# Display50_Cape.net
KiCad netlist of a schematic drawn in EAGLE
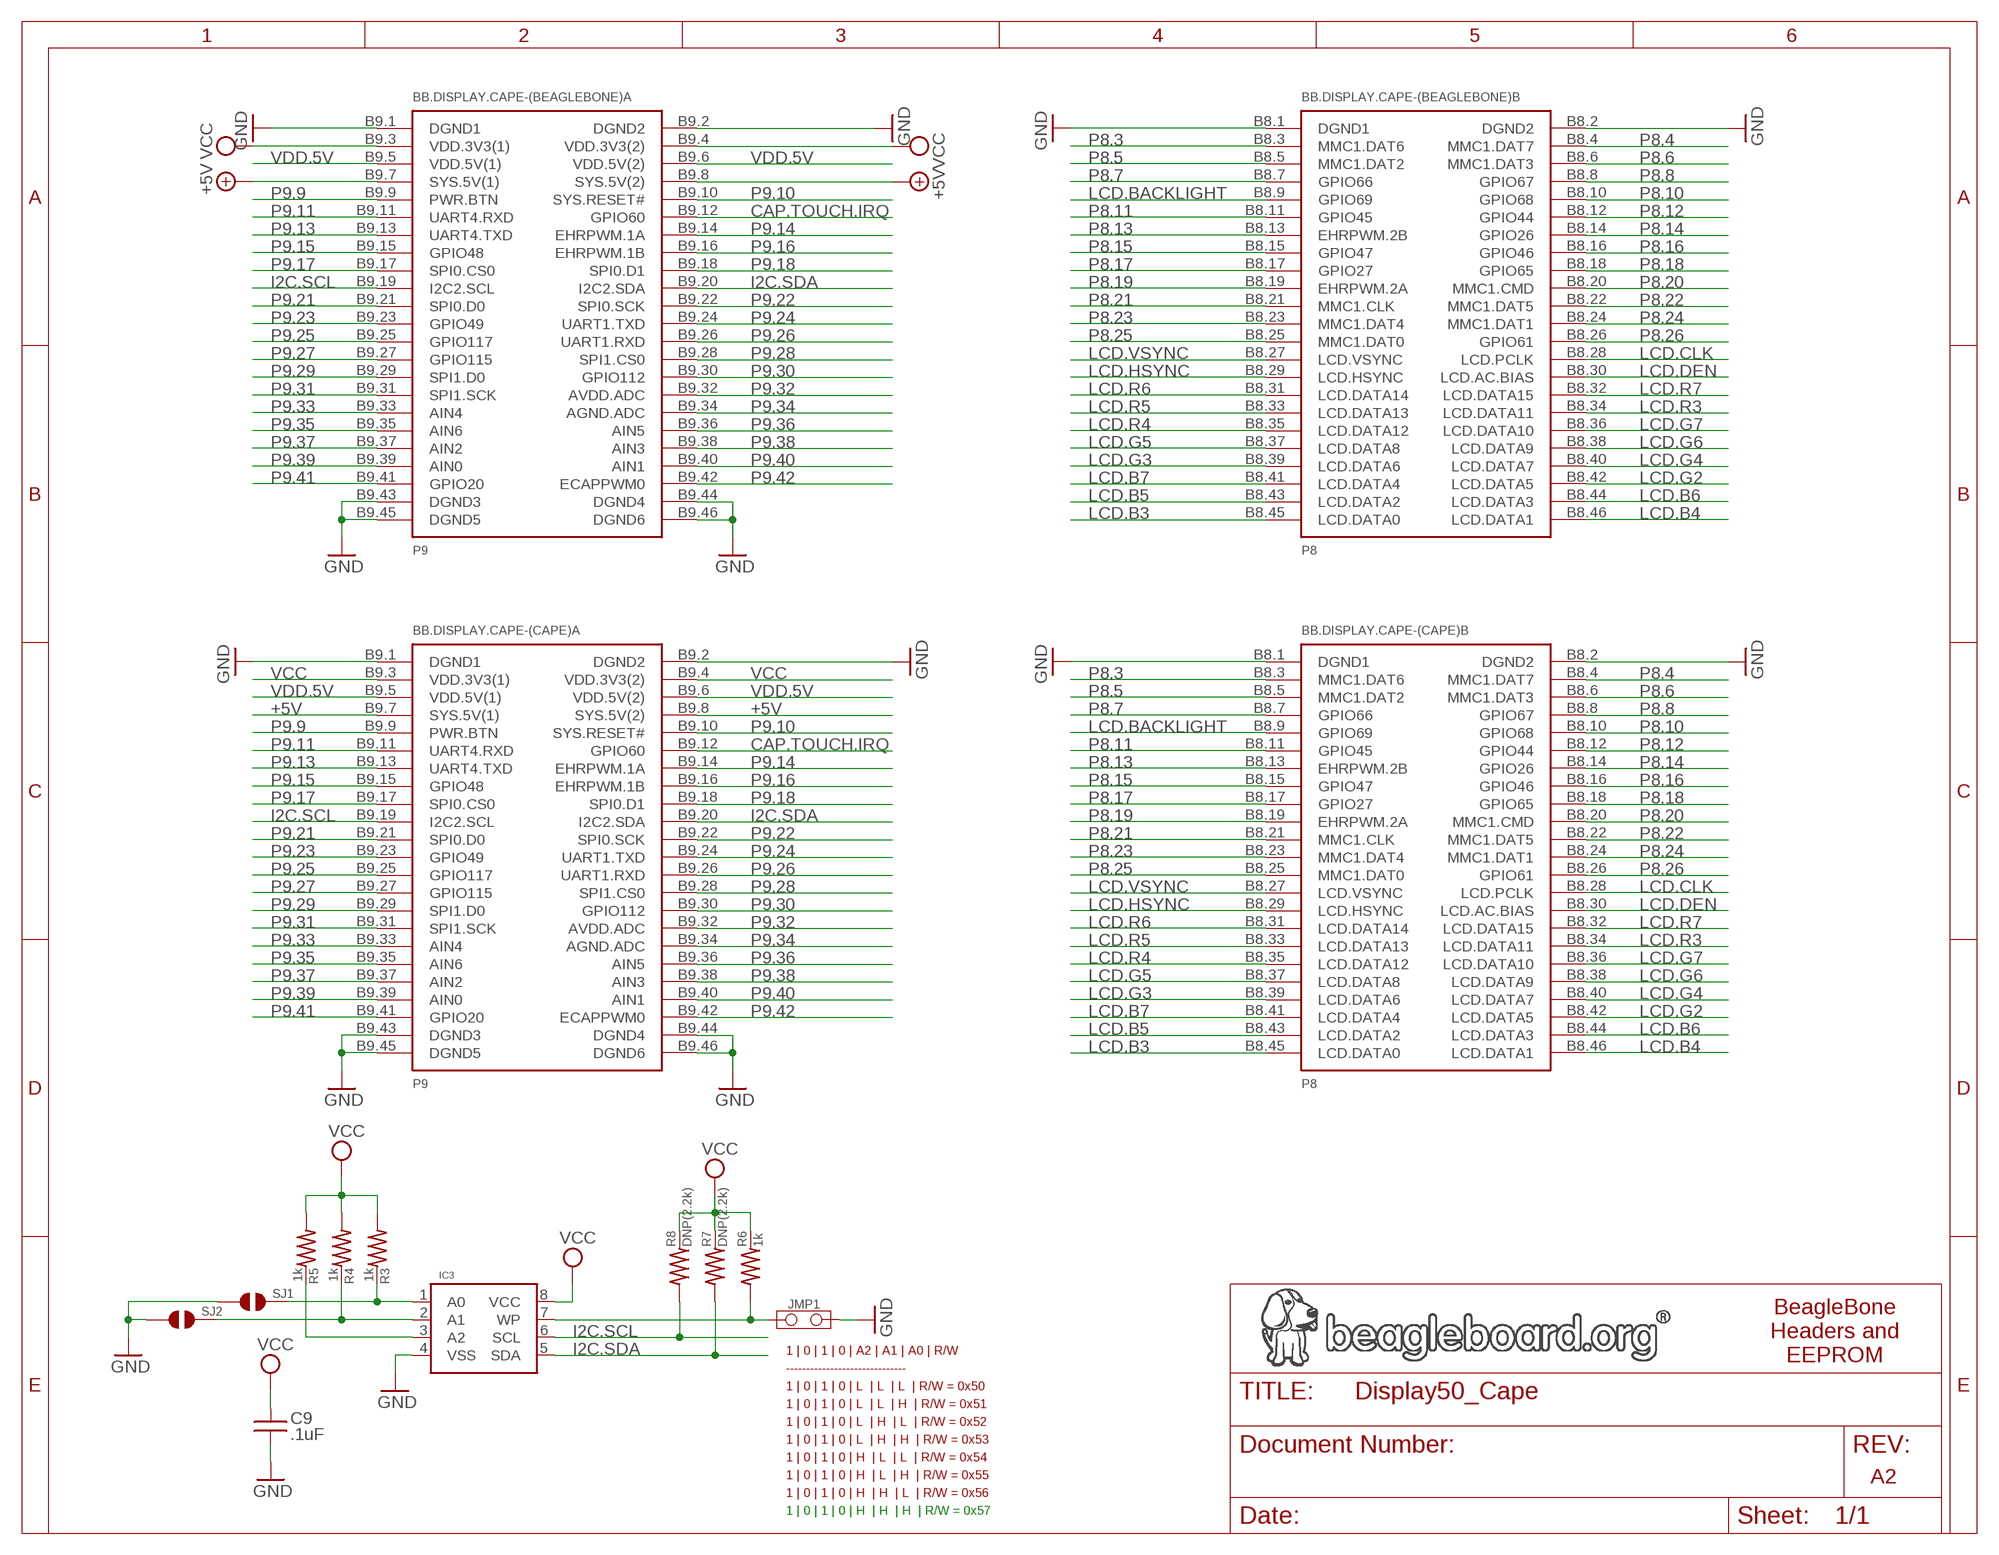
[diagram p0: schematic, sheet 1, part 1 of 2]
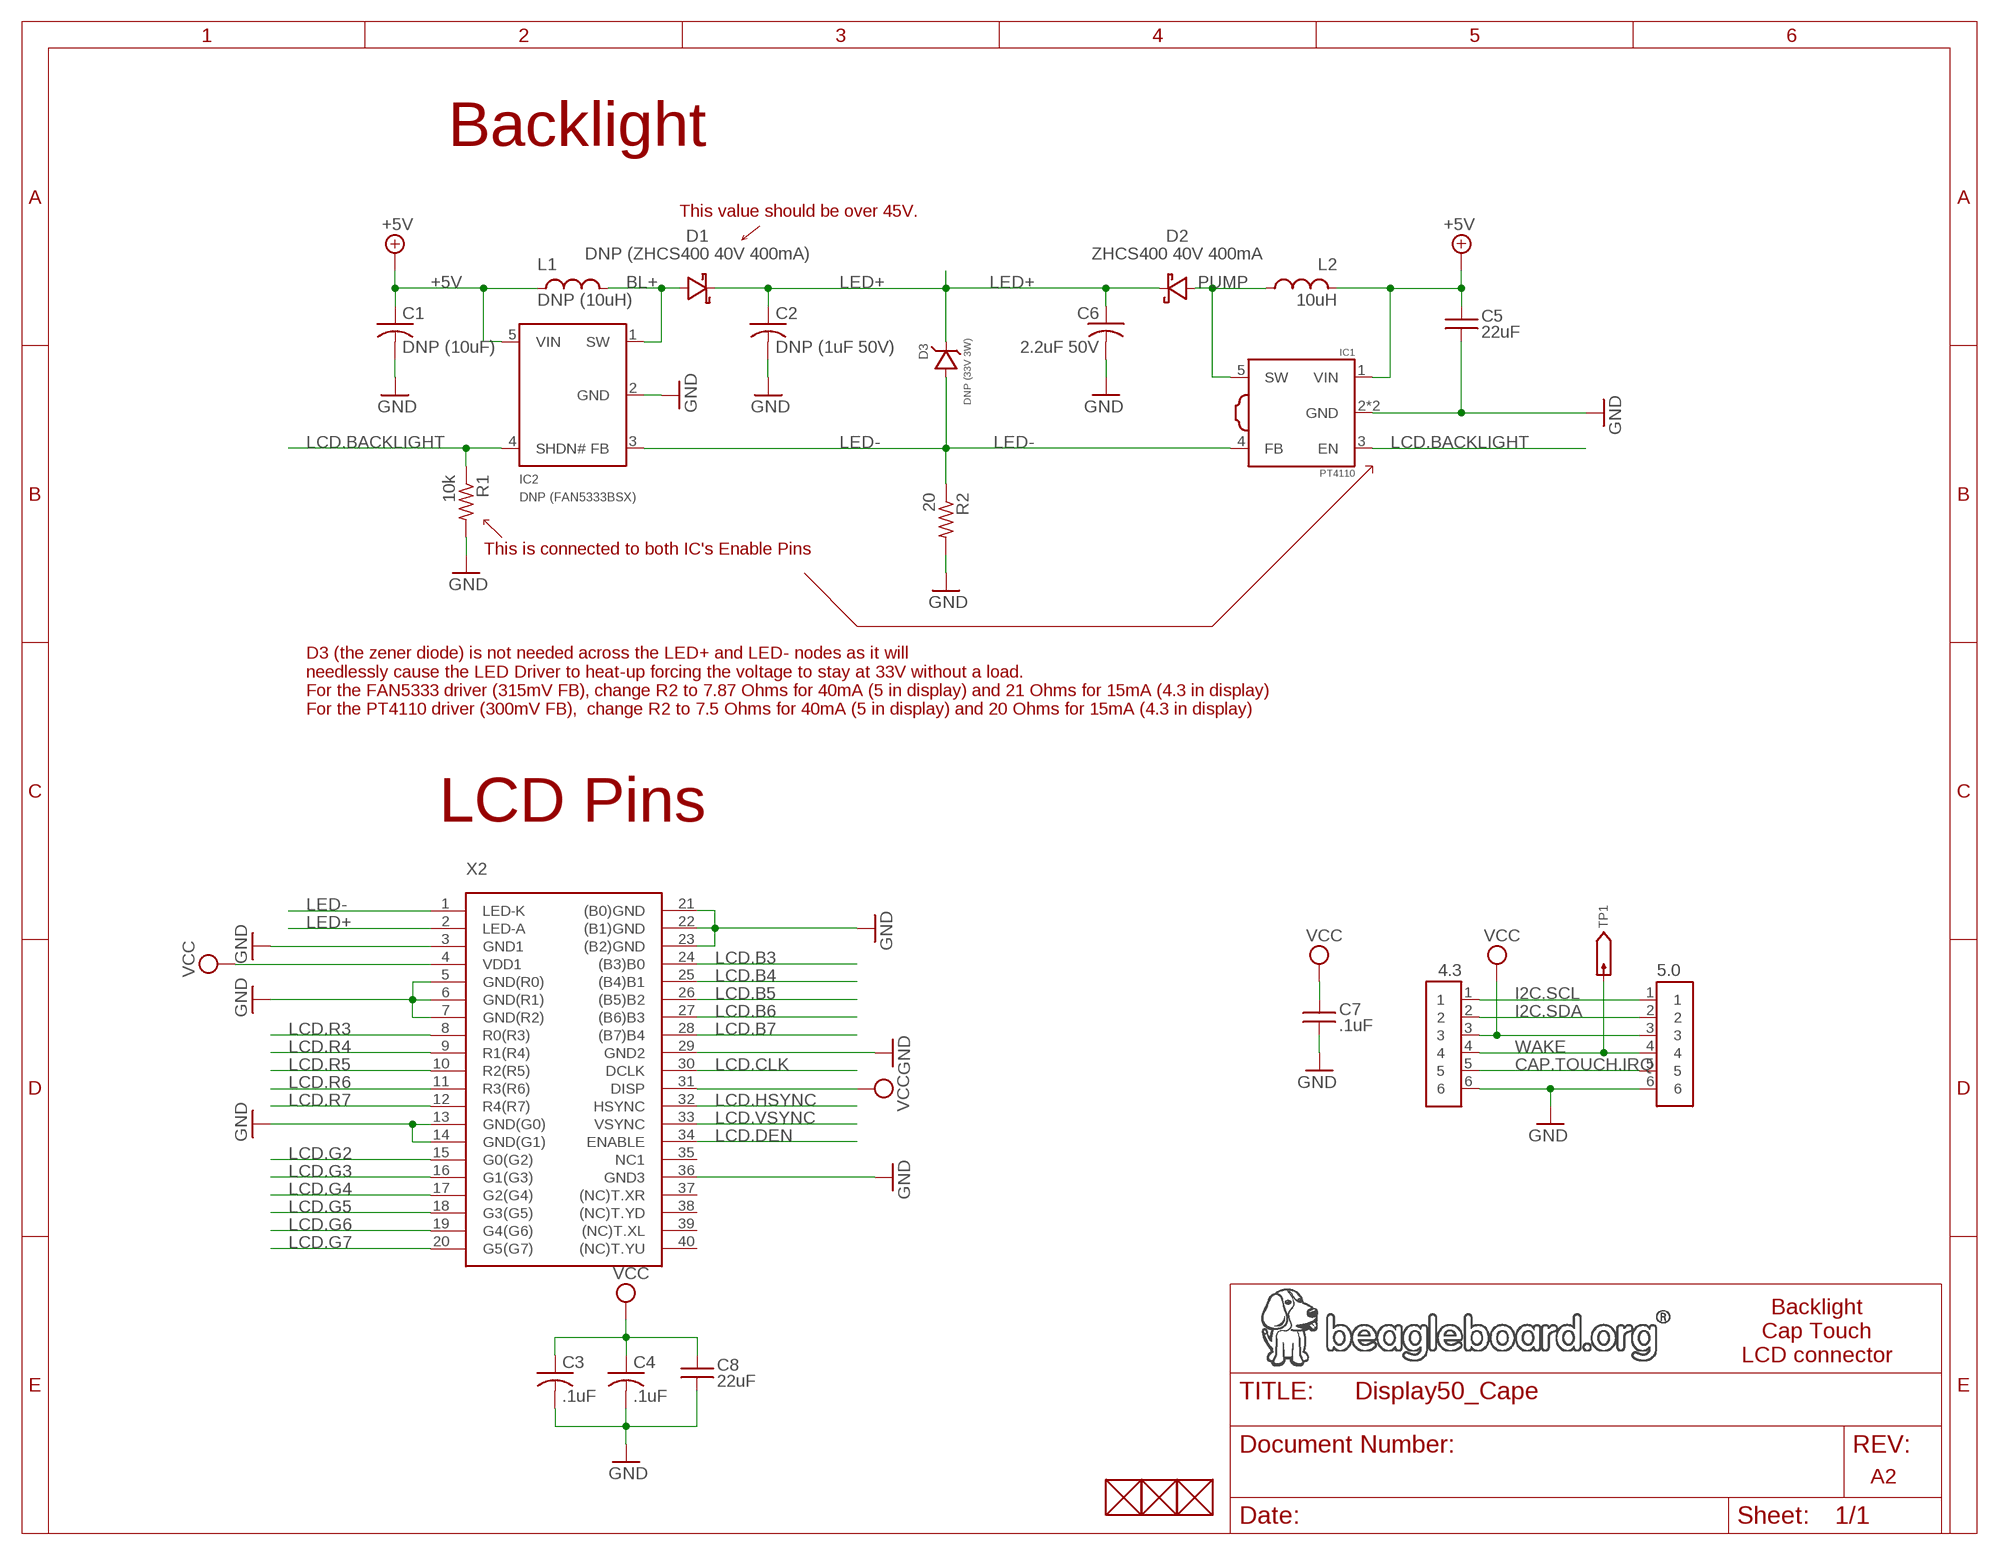
[diagram p1: schematic, sheet 1, part 2 of 2]

(export (version "E")
  (design (tool "Eeschema 10.0.6"))
  (components
    (comp (ref "4.3")
      (value "6-PIN-(0.5MM-PITCH)-FPC-CONNECTOR")
      (footprint "eagle-import:6-PIN-(0.5MM-PITCH)-FPC-CONNECTOR")
      (libsource (lib "eagle-import") (part "6-PIN-(0.5MM-PITCH)-FPC-CONNECTOR"))
    )
    (comp (ref "5.0")
      (value "6-PIN-(0.5MM-PITCH)-FPC-CONNECTOR")
      (footprint "eagle-import:6-PIN-(0.5MM-PITCH)-FPC-CONNECTOR")
      (libsource (lib "eagle-import") (part "6-PIN-(0.5MM-PITCH)-FPC-CONNECTOR"))
    )
    (comp (ref "BB.DISPLAY.CAPE-(BEAGLEBONE)")
      (value "BEAGLEBONE.CAPE.DISPLAY-X.BEAGLEBONE")
      (footprint "eagle-import:BEAGLEBONE.CAPE.DISPLAY-X.BEAGLEBONE")
      (libsource (lib "eagle-import") (part "BEAGLEBONE.CAPE.DISPLAY-X.BEAGLEBONE"))
    )
    (comp (ref "BB.DISPLAY.CAPE-(CAPE)")
      (value "BEAGLEBONE.CAPE.DISPLAY-X.CAPE")
      (footprint "eagle-import:BEAGLEBONE.CAPE.DISPLAY-X.CAPE")
      (libsource (lib "eagle-import") (part "BEAGLEBONE.CAPE.DISPLAY-X.CAPE"))
    )
    (comp (ref "C1")
      (value "DNP (10uF)")
      (footprint "eagle-import:C0603K")
      (libsource (lib "eagle-import") (part "C-USC0603K"))
    )
    (comp (ref "C2")
      (value "DNP (1uF 50V)")
      (footprint "eagle-import:C0805K")
      (libsource (lib "eagle-import") (part "C-USC0805K"))
    )
    (comp (ref "C3")
      (value ".1uF")
      (footprint "eagle-import:C0402K")
      (libsource (lib "eagle-import") (part "C-USC0402K"))
    )
    (comp (ref "C4")
      (value ".1uF")
      (footprint "eagle-import:C0402K")
      (libsource (lib "eagle-import") (part "C-USC0402K"))
    )
    (comp (ref "C5")
      (value "22uF")
      (footprint "eagle-import:0805")
      (libsource (lib "eagle-import") (part "CAPACITOR-(INCH)-0805"))
    )
    (comp (ref "C6")
      (value "2.2uF 50V")
      (footprint "eagle-import:C0805K")
      (libsource (lib "eagle-import") (part "C-USC0805K"))
    )
    (comp (ref "C7")
      (value ".1uF")
      (footprint "eagle-import:0402")
      (libsource (lib "eagle-import") (part "CAPACITOR-(INCH)-0402"))
    )
    (comp (ref "C8")
      (value "22uF")
      (footprint "eagle-import:0805")
      (libsource (lib "eagle-import") (part "CAPACITOR-(INCH)-0805"))
    )
    (comp (ref "C9")
      (value ".1uF")
      (footprint "eagle-import:0402")
      (libsource (lib "eagle-import") (part "CAPACITOR-(INCH)-0402"))
    )
    (comp (ref "D1")
      (value "DNP (ZHCS400 40V 400mA)")
      (footprint "eagle-import:SOD323(NXP)WAVE")
      (libsource (lib "eagle-import") (part "DIODE-SCHOTTKY-(NXP)-SOD323-(WAVE)"))
    )
    (comp (ref "D2")
      (value "ZHCS400 40V 400mA")
      (footprint "eagle-import:SOD323(NXP)WAVE")
      (libsource (lib "eagle-import") (part "DIODE-SCHOTTKY-(NXP)-SOD323-(WAVE)"))
    )
    (comp (ref "D3")
      (value "DNP (33V 3W)")
      (footprint "eagle-import:SMB(ON.SEMI)")
      (libsource (lib "eagle-import") (part "DIODE-ZENER-"))
    )
    (comp (ref "FUD1")
      (value "FIDUCIAL")
      (footprint "eagle-import:FIDUCIAL_40MIL")
      (libsource (lib "eagle-import") (part "FIDUCIAL"))
    )
    (comp (ref "FUD2")
      (value "FIDUCIAL")
      (footprint "eagle-import:FIDUCIAL_40MIL")
      (libsource (lib "eagle-import") (part "FIDUCIAL"))
    )
    (comp (ref "FUD3")
      (value "FIDUCIAL")
      (footprint "eagle-import:FIDUCIAL_40MIL")
      (libsource (lib "eagle-import") (part "FIDUCIAL"))
    )
    (comp (ref "IC1")
      (value "PT4110")
      (footprint "eagle-import:SOT89-5(DIODES)")
      (libsource (lib "eagle-import") (part "PT4110"))
    )
    (comp (ref "IC2")
      (value "DNP (FAN5333BSX)")
      (footprint "eagle-import:SOT23-5(FAIRCHILD)")
      (libsource (lib "eagle-import") (part "FAN533X"))
    )
    (comp (ref "IC3")
      (value "CAT24C32")
      (footprint "eagle-import:UDFN8,2X3(ON-SEMI)")
      (libsource (lib "eagle-import") (part "CAT24C32"))
    )
    (comp (ref "JMP1")
      (value "JUMPER-(X2)")
      (footprint "eagle-import:JUMPER-(X2)")
      (libsource (lib "eagle-import") (part "JUMPER-(X2)"))
    )
    (comp (ref "L1")
      (value "DNP (10uH)")
      (footprint "eagle-import:NRS(TAIYO.YUDEN)")
      (libsource (lib "eagle-import") (part "INDUCTOR-(TAIYO-YUDEN)-NRS5030"))
    )
    (comp (ref "L2")
      (value "10uH")
      (footprint "eagle-import:NRS(TAIYO.YUDEN)")
      (libsource (lib "eagle-import") (part "INDUCTOR-(TAIYO-YUDEN)-NRS5030"))
    )
    (comp (ref "R1")
      (value "10k")
      (footprint "eagle-import:R0603")
      (libsource (lib "eagle-import") (part "R-US_R0603"))
    )
    (comp (ref "R2")
      (value "20")
      (footprint "eagle-import:R0603")
      (libsource (lib "eagle-import") (part "R-US_R0603"))
    )
    (comp (ref "R3")
      (value "1k")
      (footprint "eagle-import:0402")
      (libsource (lib "eagle-import") (part "RESISTOR-(INCH)-0402"))
    )
    (comp (ref "R4")
      (value "1k")
      (footprint "eagle-import:0402")
      (libsource (lib "eagle-import") (part "RESISTOR-(INCH)-0402"))
    )
    (comp (ref "R5")
      (value "1k")
      (footprint "eagle-import:0402")
      (libsource (lib "eagle-import") (part "RESISTOR-(INCH)-0402"))
    )
    (comp (ref "R6")
      (value "1k")
      (footprint "eagle-import:0402")
      (libsource (lib "eagle-import") (part "RESISTOR-(INCH)-0402"))
    )
    (comp (ref "R7")
      (value "DNP(2.2k)")
      (footprint "eagle-import:0402")
      (libsource (lib "eagle-import") (part "RESISTOR-(INCH)-0402"))
    )
    (comp (ref "R8")
      (value "DNP(2.2k)")
      (footprint "eagle-import:0402")
      (libsource (lib "eagle-import") (part "RESISTOR-(INCH)-0402"))
    )
    (comp (ref "SJ1")
      (value "SOLDER.JOINT-(INCH)-0402")
      (footprint "eagle-import:SOLDER.JOINT(0402)")
      (libsource (lib "eagle-import") (part "SOLDER.JOINT-(INCH)-0402"))
    )
    (comp (ref "SJ2")
      (value "SOLDER.JOINT-(INCH)-0402")
      (footprint "eagle-import:SOLDER.JOINT(0402)")
      (libsource (lib "eagle-import") (part "SOLDER.JOINT-(INCH)-0402"))
    )
    (comp (ref "TP1")
      (value "TESTPAD/W_HOLE_1X1")
      (footprint "eagle-import:TESTPAD_W_HOLE_1X1")
      (libsource (lib "eagle-import") (part "TESTPAD/W_HOLE_1X1"))
    )
    (comp (ref "X2")
      (value "LCD-40PIN_FFC/FPC_0.5MM_PITCH")
      (footprint "eagle-import:KISD04-40_T1_E")
      (libsource (lib "eagle-import") (part "LCD-40PIN_FFC/FPC_0.5MM_PITCH"))
    )
  )
  (nets
    (net (code "1") (name "+5V") (class "Default")
      (node (ref "BB.DISPLAY.CAPE-(BEAGLEBONE)") (pin "B9.7") (pinfunction "SYS.5V(1)_B9.7") (pintype "bidirectional"))
      (node (ref "BB.DISPLAY.CAPE-(BEAGLEBONE)") (pin "B9.8") (pinfunction "SYS.5V(2)_B9.8") (pintype "bidirectional"))
      (node (ref "BB.DISPLAY.CAPE-(CAPE)") (pin "B9.7") (pinfunction "SYS.5V(1)_B9.7") (pintype "bidirectional"))
      (node (ref "BB.DISPLAY.CAPE-(CAPE)") (pin "B9.8") (pinfunction "SYS.5V(2)_B9.8") (pintype "bidirectional"))
      (node (ref "C1") (pin "1") (pinfunction "1_1") (pintype "passive"))
      (node (ref "C5") (pin "1") (pinfunction "1_1") (pintype "bidirectional"))
      (node (ref "IC1") (pin "1") (pinfunction "VIN_1") (pintype "bidirectional"))
      (node (ref "IC2") (pin "5") (pinfunction "VIN_5") (pintype "bidirectional"))
      (node (ref "L1") (pin "1") (pinfunction "1_1") (pintype "bidirectional"))
      (node (ref "L2") (pin "1") (pinfunction "1_1") (pintype "bidirectional"))
    )
    (net (code "2") (name "/BL+") (class "Default")
      (node (ref "D1") (pin "A") (pinfunction "ANODE_A") (pintype "bidirectional"))
      (node (ref "IC2") (pin "1") (pinfunction "SW_1") (pintype "bidirectional"))
      (node (ref "L1") (pin "2") (pinfunction "2_2") (pintype "bidirectional"))
    )
    (net (code "3") (name "/CAP.TOUCH.IRQ") (class "Default")
      (node (ref "4.3") (pin "5") (pinfunction "5_5") (pintype "bidirectional"))
      (node (ref "5.0") (pin "5") (pinfunction "5_5") (pintype "bidirectional"))
      (node (ref "BB.DISPLAY.CAPE-(BEAGLEBONE)") (pin "B9.12") (pinfunction "GPIO60_B9.12") (pintype "bidirectional"))
      (node (ref "BB.DISPLAY.CAPE-(CAPE)") (pin "B9.12") (pinfunction "GPIO60_B9.12") (pintype "bidirectional"))
    )
    (net (code "4") (name "/I2C.SCL") (class "Default")
      (node (ref "4.3") (pin "1") (pinfunction "1_1") (pintype "bidirectional"))
      (node (ref "5.0") (pin "1") (pinfunction "1_1") (pintype "bidirectional"))
      (node (ref "BB.DISPLAY.CAPE-(BEAGLEBONE)") (pin "B9.19") (pinfunction "I2C2.SCL_B9.19") (pintype "bidirectional"))
      (node (ref "BB.DISPLAY.CAPE-(CAPE)") (pin "B9.19") (pinfunction "I2C2.SCL_B9.19") (pintype "bidirectional"))
      (node (ref "IC3") (pin "6") (pinfunction "SCL_6") (pintype "bidirectional"))
      (node (ref "R8") (pin "1") (pinfunction "1_1") (pintype "bidirectional"))
    )
    (net (code "5") (name "/I2C.SDA") (class "Default")
      (node (ref "4.3") (pin "2") (pinfunction "2_2") (pintype "bidirectional"))
      (node (ref "5.0") (pin "2") (pinfunction "2_2") (pintype "bidirectional"))
      (node (ref "BB.DISPLAY.CAPE-(BEAGLEBONE)") (pin "B9.20") (pinfunction "I2C2.SDA_B9.20") (pintype "bidirectional"))
      (node (ref "BB.DISPLAY.CAPE-(CAPE)") (pin "B9.20") (pinfunction "I2C2.SDA_B9.20") (pintype "bidirectional"))
      (node (ref "IC3") (pin "5") (pinfunction "SDA_5") (pintype "bidirectional"))
      (node (ref "R7") (pin "1") (pinfunction "1_1") (pintype "bidirectional"))
    )
    (net (code "6") (name "/LCD.B3") (class "Default")
      (node (ref "BB.DISPLAY.CAPE-(BEAGLEBONE)") (pin "B8.45") (pinfunction "LCD.DATA0_B8.45") (pintype "bidirectional"))
      (node (ref "BB.DISPLAY.CAPE-(CAPE)") (pin "B8.45") (pinfunction "LCD.DATA0_B8.45") (pintype "bidirectional"))
      (node (ref "X2") (pin "24") (pinfunction "(B3)B0_24") (pintype "bidirectional"))
    )
    (net (code "7") (name "/LCD.B4") (class "Default")
      (node (ref "BB.DISPLAY.CAPE-(BEAGLEBONE)") (pin "B8.46") (pinfunction "LCD.DATA1_B8.46") (pintype "bidirectional"))
      (node (ref "BB.DISPLAY.CAPE-(CAPE)") (pin "B8.46") (pinfunction "LCD.DATA1_B8.46") (pintype "bidirectional"))
      (node (ref "X2") (pin "25") (pinfunction "(B4)B1_25") (pintype "bidirectional"))
    )
    (net (code "8") (name "/LCD.B5") (class "Default")
      (node (ref "BB.DISPLAY.CAPE-(BEAGLEBONE)") (pin "B8.43") (pinfunction "LCD.DATA2_B8.43") (pintype "bidirectional"))
      (node (ref "BB.DISPLAY.CAPE-(CAPE)") (pin "B8.43") (pinfunction "LCD.DATA2_B8.43") (pintype "bidirectional"))
      (node (ref "X2") (pin "26") (pinfunction "(B5)B2_26") (pintype "bidirectional"))
    )
    (net (code "9") (name "/LCD.B6") (class "Default")
      (node (ref "BB.DISPLAY.CAPE-(BEAGLEBONE)") (pin "B8.44") (pinfunction "LCD.DATA3_B8.44") (pintype "bidirectional"))
      (node (ref "BB.DISPLAY.CAPE-(CAPE)") (pin "B8.44") (pinfunction "LCD.DATA3_B8.44") (pintype "bidirectional"))
      (node (ref "X2") (pin "27") (pinfunction "(B6)B3_27") (pintype "bidirectional"))
    )
    (net (code "10") (name "/LCD.B7") (class "Default")
      (node (ref "BB.DISPLAY.CAPE-(BEAGLEBONE)") (pin "B8.41") (pinfunction "LCD.DATA4_B8.41") (pintype "bidirectional"))
      (node (ref "BB.DISPLAY.CAPE-(CAPE)") (pin "B8.41") (pinfunction "LCD.DATA4_B8.41") (pintype "bidirectional"))
      (node (ref "X2") (pin "28") (pinfunction "(B7)B4_28") (pintype "bidirectional"))
    )
    (net (code "11") (name "/LCD.BACKLIGHT") (class "Default")
      (node (ref "BB.DISPLAY.CAPE-(BEAGLEBONE)") (pin "B8.9") (pinfunction "GPIO69_B8.9") (pintype "bidirectional"))
      (node (ref "BB.DISPLAY.CAPE-(CAPE)") (pin "B8.9") (pinfunction "GPIO69_B8.9") (pintype "bidirectional"))
      (node (ref "IC1") (pin "3") (pinfunction "EN_3") (pintype "bidirectional"))
      (node (ref "IC2") (pin "4") (pinfunction "SHDN#_4") (pintype "bidirectional"))
      (node (ref "R1") (pin "1") (pinfunction "1_1") (pintype "passive"))
    )
    (net (code "12") (name "/LCD.CLK") (class "Default")
      (node (ref "BB.DISPLAY.CAPE-(BEAGLEBONE)") (pin "B8.28") (pinfunction "LCD.PCLK_B8.28") (pintype "bidirectional"))
      (node (ref "BB.DISPLAY.CAPE-(CAPE)") (pin "B8.28") (pinfunction "LCD.PCLK_B8.28") (pintype "bidirectional"))
      (node (ref "X2") (pin "30") (pinfunction "DCLK_30") (pintype "bidirectional"))
    )
    (net (code "13") (name "/LCD.DEN") (class "Default")
      (node (ref "BB.DISPLAY.CAPE-(BEAGLEBONE)") (pin "B8.30") (pinfunction "LCD.AC.BIAS_B8.30") (pintype "bidirectional"))
      (node (ref "BB.DISPLAY.CAPE-(CAPE)") (pin "B8.30") (pinfunction "LCD.AC.BIAS_B8.30") (pintype "bidirectional"))
      (node (ref "X2") (pin "34") (pinfunction "ENABLE_34") (pintype "bidirectional"))
    )
    (net (code "14") (name "/LCD.G2") (class "Default")
      (node (ref "BB.DISPLAY.CAPE-(BEAGLEBONE)") (pin "B8.42") (pinfunction "LCD.DATA5_B8.42") (pintype "bidirectional"))
      (node (ref "BB.DISPLAY.CAPE-(CAPE)") (pin "B8.42") (pinfunction "LCD.DATA5_B8.42") (pintype "bidirectional"))
      (node (ref "X2") (pin "15") (pinfunction "G0(G2)_15") (pintype "bidirectional"))
    )
    (net (code "15") (name "/LCD.G3") (class "Default")
      (node (ref "BB.DISPLAY.CAPE-(BEAGLEBONE)") (pin "B8.39") (pinfunction "LCD.DATA6_B8.39") (pintype "bidirectional"))
      (node (ref "BB.DISPLAY.CAPE-(CAPE)") (pin "B8.39") (pinfunction "LCD.DATA6_B8.39") (pintype "bidirectional"))
      (node (ref "X2") (pin "16") (pinfunction "G1(G3)_16") (pintype "bidirectional"))
    )
    (net (code "16") (name "/LCD.G4") (class "Default")
      (node (ref "BB.DISPLAY.CAPE-(BEAGLEBONE)") (pin "B8.40") (pinfunction "LCD.DATA7_B8.40") (pintype "bidirectional"))
      (node (ref "BB.DISPLAY.CAPE-(CAPE)") (pin "B8.40") (pinfunction "LCD.DATA7_B8.40") (pintype "bidirectional"))
      (node (ref "X2") (pin "17") (pinfunction "G2(G4)_17") (pintype "bidirectional"))
    )
    (net (code "17") (name "/LCD.G5") (class "Default")
      (node (ref "BB.DISPLAY.CAPE-(BEAGLEBONE)") (pin "B8.37") (pinfunction "LCD.DATA8_B8.37") (pintype "bidirectional"))
      (node (ref "BB.DISPLAY.CAPE-(CAPE)") (pin "B8.37") (pinfunction "LCD.DATA8_B8.37") (pintype "bidirectional"))
      (node (ref "X2") (pin "18") (pinfunction "G3(G5)_18") (pintype "bidirectional"))
    )
    (net (code "18") (name "/LCD.G6") (class "Default")
      (node (ref "BB.DISPLAY.CAPE-(BEAGLEBONE)") (pin "B8.38") (pinfunction "LCD.DATA9_B8.38") (pintype "bidirectional"))
      (node (ref "BB.DISPLAY.CAPE-(CAPE)") (pin "B8.38") (pinfunction "LCD.DATA9_B8.38") (pintype "bidirectional"))
      (node (ref "X2") (pin "19") (pinfunction "G4(G6)_19") (pintype "bidirectional"))
    )
    (net (code "19") (name "/LCD.G7") (class "Default")
      (node (ref "BB.DISPLAY.CAPE-(BEAGLEBONE)") (pin "B8.36") (pinfunction "LCD.DATA10_B8.36") (pintype "bidirectional"))
      (node (ref "BB.DISPLAY.CAPE-(CAPE)") (pin "B8.36") (pinfunction "LCD.DATA10_B8.36") (pintype "bidirectional"))
      (node (ref "X2") (pin "20") (pinfunction "G5(G7)_20") (pintype "bidirectional"))
    )
    (net (code "20") (name "/LCD.HSYNC") (class "Default")
      (node (ref "BB.DISPLAY.CAPE-(BEAGLEBONE)") (pin "B8.29") (pinfunction "LCD.HSYNC_B8.29") (pintype "bidirectional"))
      (node (ref "BB.DISPLAY.CAPE-(CAPE)") (pin "B8.29") (pinfunction "LCD.HSYNC_B8.29") (pintype "bidirectional"))
      (node (ref "X2") (pin "32") (pinfunction "HSYNC_32") (pintype "bidirectional"))
    )
    (net (code "21") (name "/LCD.R3") (class "Default")
      (node (ref "BB.DISPLAY.CAPE-(BEAGLEBONE)") (pin "B8.34") (pinfunction "LCD.DATA11_B8.34") (pintype "bidirectional"))
      (node (ref "BB.DISPLAY.CAPE-(CAPE)") (pin "B8.34") (pinfunction "LCD.DATA11_B8.34") (pintype "bidirectional"))
      (node (ref "X2") (pin "8") (pinfunction "R0(R3)_8") (pintype "bidirectional"))
    )
    (net (code "22") (name "/LCD.R4") (class "Default")
      (node (ref "BB.DISPLAY.CAPE-(BEAGLEBONE)") (pin "B8.35") (pinfunction "LCD.DATA12_B8.35") (pintype "bidirectional"))
      (node (ref "BB.DISPLAY.CAPE-(CAPE)") (pin "B8.35") (pinfunction "LCD.DATA12_B8.35") (pintype "bidirectional"))
      (node (ref "X2") (pin "9") (pinfunction "R1(R4)_9") (pintype "bidirectional"))
    )
    (net (code "23") (name "/LCD.R5") (class "Default")
      (node (ref "BB.DISPLAY.CAPE-(BEAGLEBONE)") (pin "B8.33") (pinfunction "LCD.DATA13_B8.33") (pintype "bidirectional"))
      (node (ref "BB.DISPLAY.CAPE-(CAPE)") (pin "B8.33") (pinfunction "LCD.DATA13_B8.33") (pintype "bidirectional"))
      (node (ref "X2") (pin "10") (pinfunction "R2(R5)_10") (pintype "bidirectional"))
    )
    (net (code "24") (name "/LCD.R6") (class "Default")
      (node (ref "BB.DISPLAY.CAPE-(BEAGLEBONE)") (pin "B8.31") (pinfunction "LCD.DATA14_B8.31") (pintype "bidirectional"))
      (node (ref "BB.DISPLAY.CAPE-(CAPE)") (pin "B8.31") (pinfunction "LCD.DATA14_B8.31") (pintype "bidirectional"))
      (node (ref "X2") (pin "11") (pinfunction "R3(R6)_11") (pintype "bidirectional"))
    )
    (net (code "25") (name "/LCD.R7") (class "Default")
      (node (ref "BB.DISPLAY.CAPE-(BEAGLEBONE)") (pin "B8.32") (pinfunction "LCD.DATA15_B8.32") (pintype "bidirectional"))
      (node (ref "BB.DISPLAY.CAPE-(CAPE)") (pin "B8.32") (pinfunction "LCD.DATA15_B8.32") (pintype "bidirectional"))
      (node (ref "X2") (pin "12") (pinfunction "R4(R7)_12") (pintype "bidirectional"))
    )
    (net (code "26") (name "/LCD.VSYNC") (class "Default")
      (node (ref "BB.DISPLAY.CAPE-(BEAGLEBONE)") (pin "B8.27") (pinfunction "LCD.VSYNC_B8.27") (pintype "bidirectional"))
      (node (ref "BB.DISPLAY.CAPE-(CAPE)") (pin "B8.27") (pinfunction "LCD.VSYNC_B8.27") (pintype "bidirectional"))
      (node (ref "X2") (pin "33") (pinfunction "VSYNC_33") (pintype "bidirectional"))
    )
    (net (code "27") (name "/LED+") (class "Default")
      (node (ref "C2") (pin "1") (pinfunction "1_1") (pintype "passive"))
      (node (ref "C6") (pin "1") (pinfunction "1_1") (pintype "passive"))
      (node (ref "D1") (pin "C") (pinfunction "CATHODE_C") (pintype "bidirectional"))
      (node (ref "D2") (pin "C") (pinfunction "CATHODE_C") (pintype "bidirectional"))
      (node (ref "D3") (pin "K") (pinfunction "K_K") (pintype "bidirectional"))
      (node (ref "X2") (pin "2") (pinfunction "LED-A_2") (pintype "bidirectional"))
    )
    (net (code "28") (name "/LED-") (class "Default")
      (node (ref "D3") (pin "A") (pinfunction "A_A") (pintype "bidirectional"))
      (node (ref "IC1") (pin "4") (pinfunction "FB_4") (pintype "bidirectional"))
      (node (ref "IC2") (pin "3") (pinfunction "FB_3") (pintype "bidirectional"))
      (node (ref "R2") (pin "1") (pinfunction "1_1") (pintype "passive"))
      (node (ref "X2") (pin "1") (pinfunction "LED-K_1") (pintype "bidirectional"))
    )
    (net (code "29") (name "/P8.3") (class "Default")
      (node (ref "BB.DISPLAY.CAPE-(BEAGLEBONE)") (pin "B8.3") (pinfunction "MMC1.DAT6_B8.3") (pintype "bidirectional"))
      (node (ref "BB.DISPLAY.CAPE-(CAPE)") (pin "B8.3") (pinfunction "MMC1.DAT6_B8.3") (pintype "bidirectional"))
    )
    (net (code "30") (name "/P8.4") (class "Default")
      (node (ref "BB.DISPLAY.CAPE-(BEAGLEBONE)") (pin "B8.4") (pinfunction "MMC1.DAT7_B8.4") (pintype "bidirectional"))
      (node (ref "BB.DISPLAY.CAPE-(CAPE)") (pin "B8.4") (pinfunction "MMC1.DAT7_B8.4") (pintype "bidirectional"))
    )
    (net (code "31") (name "/P8.5") (class "Default")
      (node (ref "BB.DISPLAY.CAPE-(BEAGLEBONE)") (pin "B8.5") (pinfunction "MMC1.DAT2_B8.5") (pintype "bidirectional"))
      (node (ref "BB.DISPLAY.CAPE-(CAPE)") (pin "B8.5") (pinfunction "MMC1.DAT2_B8.5") (pintype "bidirectional"))
    )
    (net (code "32") (name "/P8.6") (class "Default")
      (node (ref "BB.DISPLAY.CAPE-(BEAGLEBONE)") (pin "B8.6") (pinfunction "MMC1.DAT3_B8.6") (pintype "bidirectional"))
      (node (ref "BB.DISPLAY.CAPE-(CAPE)") (pin "B8.6") (pinfunction "MMC1.DAT3_B8.6") (pintype "bidirectional"))
    )
    (net (code "33") (name "/P8.7") (class "Default")
      (node (ref "BB.DISPLAY.CAPE-(BEAGLEBONE)") (pin "B8.7") (pinfunction "GPIO66_B8.7") (pintype "bidirectional"))
      (node (ref "BB.DISPLAY.CAPE-(CAPE)") (pin "B8.7") (pinfunction "GPIO66_B8.7") (pintype "bidirectional"))
    )
    (net (code "34") (name "/P8.8") (class "Default")
      (node (ref "BB.DISPLAY.CAPE-(BEAGLEBONE)") (pin "B8.8") (pinfunction "GPIO67_B8.8") (pintype "bidirectional"))
      (node (ref "BB.DISPLAY.CAPE-(CAPE)") (pin "B8.8") (pinfunction "GPIO67_B8.8") (pintype "bidirectional"))
    )
    (net (code "35") (name "/P8.10") (class "Default")
      (node (ref "BB.DISPLAY.CAPE-(BEAGLEBONE)") (pin "B8.10") (pinfunction "GPIO68_B8.10") (pintype "bidirectional"))
      (node (ref "BB.DISPLAY.CAPE-(CAPE)") (pin "B8.10") (pinfunction "GPIO68_B8.10") (pintype "bidirectional"))
    )
    (net (code "36") (name "/P8.11") (class "Default")
      (node (ref "BB.DISPLAY.CAPE-(BEAGLEBONE)") (pin "B8.11") (pinfunction "GPIO45_B8.11") (pintype "bidirectional"))
      (node (ref "BB.DISPLAY.CAPE-(CAPE)") (pin "B8.11") (pinfunction "GPIO45_B8.11") (pintype "bidirectional"))
    )
    (net (code "37") (name "/P8.12") (class "Default")
      (node (ref "BB.DISPLAY.CAPE-(BEAGLEBONE)") (pin "B8.12") (pinfunction "GPIO44_B8.12") (pintype "bidirectional"))
      (node (ref "BB.DISPLAY.CAPE-(CAPE)") (pin "B8.12") (pinfunction "GPIO44_B8.12") (pintype "bidirectional"))
    )
    (net (code "38") (name "/P8.13") (class "Default")
      (node (ref "BB.DISPLAY.CAPE-(BEAGLEBONE)") (pin "B8.13") (pinfunction "EHRPWM.2B_B8.13") (pintype "bidirectional"))
      (node (ref "BB.DISPLAY.CAPE-(CAPE)") (pin "B8.13") (pinfunction "EHRPWM.2B_B8.13") (pintype "bidirectional"))
    )
    (net (code "39") (name "/P8.14") (class "Default")
      (node (ref "BB.DISPLAY.CAPE-(BEAGLEBONE)") (pin "B8.14") (pinfunction "GPIO26_B8.14") (pintype "bidirectional"))
      (node (ref "BB.DISPLAY.CAPE-(CAPE)") (pin "B8.14") (pinfunction "GPIO26_B8.14") (pintype "bidirectional"))
    )
    (net (code "40") (name "/P8.15") (class "Default")
      (node (ref "BB.DISPLAY.CAPE-(BEAGLEBONE)") (pin "B8.15") (pinfunction "GPIO47_B8.15") (pintype "bidirectional"))
      (node (ref "BB.DISPLAY.CAPE-(CAPE)") (pin "B8.15") (pinfunction "GPIO47_B8.15") (pintype "bidirectional"))
    )
    (net (code "41") (name "/P8.16") (class "Default")
      (node (ref "BB.DISPLAY.CAPE-(BEAGLEBONE)") (pin "B8.16") (pinfunction "GPIO46_B8.16") (pintype "bidirectional"))
      (node (ref "BB.DISPLAY.CAPE-(CAPE)") (pin "B8.16") (pinfunction "GPIO46_B8.16") (pintype "bidirectional"))
    )
    (net (code "42") (name "/P8.17") (class "Default")
      (node (ref "BB.DISPLAY.CAPE-(BEAGLEBONE)") (pin "B8.17") (pinfunction "GPIO27_B8.17") (pintype "bidirectional"))
      (node (ref "BB.DISPLAY.CAPE-(CAPE)") (pin "B8.17") (pinfunction "GPIO27_B8.17") (pintype "bidirectional"))
    )
    (net (code "43") (name "/P8.18") (class "Default")
      (node (ref "BB.DISPLAY.CAPE-(BEAGLEBONE)") (pin "B8.18") (pinfunction "GPIO65_B8.18") (pintype "bidirectional"))
      (node (ref "BB.DISPLAY.CAPE-(CAPE)") (pin "B8.18") (pinfunction "GPIO65_B8.18") (pintype "bidirectional"))
    )
    (net (code "44") (name "/P8.19") (class "Default")
      (node (ref "BB.DISPLAY.CAPE-(BEAGLEBONE)") (pin "B8.19") (pinfunction "EHRPWM.2A_B8.19") (pintype "bidirectional"))
      (node (ref "BB.DISPLAY.CAPE-(CAPE)") (pin "B8.19") (pinfunction "EHRPWM.2A_B8.19") (pintype "bidirectional"))
    )
    (net (code "45") (name "/P8.20") (class "Default")
      (node (ref "BB.DISPLAY.CAPE-(BEAGLEBONE)") (pin "B8.20") (pinfunction "MMC1.CMD_B8.20") (pintype "bidirectional"))
      (node (ref "BB.DISPLAY.CAPE-(CAPE)") (pin "B8.20") (pinfunction "MMC1.CMD_B8.20") (pintype "bidirectional"))
    )
    (net (code "46") (name "/P8.21") (class "Default")
      (node (ref "BB.DISPLAY.CAPE-(BEAGLEBONE)") (pin "B8.21") (pinfunction "MMC1.CLK_B8.21") (pintype "bidirectional"))
      (node (ref "BB.DISPLAY.CAPE-(CAPE)") (pin "B8.21") (pinfunction "MMC1.CLK_B8.21") (pintype "bidirectional"))
    )
    (net (code "47") (name "/P8.22") (class "Default")
      (node (ref "BB.DISPLAY.CAPE-(BEAGLEBONE)") (pin "B8.22") (pinfunction "MMC1.DAT5_B8.22") (pintype "bidirectional"))
      (node (ref "BB.DISPLAY.CAPE-(CAPE)") (pin "B8.22") (pinfunction "MMC1.DAT5_B8.22") (pintype "bidirectional"))
    )
    (net (code "48") (name "/P8.23") (class "Default")
      (node (ref "BB.DISPLAY.CAPE-(BEAGLEBONE)") (pin "B8.23") (pinfunction "MMC1.DAT4_B8.23") (pintype "bidirectional"))
      (node (ref "BB.DISPLAY.CAPE-(CAPE)") (pin "B8.23") (pinfunction "MMC1.DAT4_B8.23") (pintype "bidirectional"))
    )
    (net (code "49") (name "/P8.24") (class "Default")
      (node (ref "BB.DISPLAY.CAPE-(BEAGLEBONE)") (pin "B8.24") (pinfunction "MMC1.DAT1_B8.24") (pintype "bidirectional"))
      (node (ref "BB.DISPLAY.CAPE-(CAPE)") (pin "B8.24") (pinfunction "MMC1.DAT1_B8.24") (pintype "bidirectional"))
    )
    (net (code "50") (name "/P8.25") (class "Default")
      (node (ref "BB.DISPLAY.CAPE-(BEAGLEBONE)") (pin "B8.25") (pinfunction "MMC1.DAT0_B8.25") (pintype "bidirectional"))
      (node (ref "BB.DISPLAY.CAPE-(CAPE)") (pin "B8.25") (pinfunction "MMC1.DAT0_B8.25") (pintype "bidirectional"))
    )
    (net (code "51") (name "/P8.26") (class "Default")
      (node (ref "BB.DISPLAY.CAPE-(BEAGLEBONE)") (pin "B8.26") (pinfunction "GPIO61_B8.26") (pintype "bidirectional"))
      (node (ref "BB.DISPLAY.CAPE-(CAPE)") (pin "B8.26") (pinfunction "GPIO61_B8.26") (pintype "bidirectional"))
    )
    (net (code "52") (name "/P9.9") (class "Default")
      (node (ref "BB.DISPLAY.CAPE-(BEAGLEBONE)") (pin "B9.9") (pinfunction "PWR.BTN_B9.9") (pintype "bidirectional"))
      (node (ref "BB.DISPLAY.CAPE-(CAPE)") (pin "B9.9") (pinfunction "PWR.BTN_B9.9") (pintype "bidirectional"))
    )
    (net (code "53") (name "/P9.10") (class "Default")
      (node (ref "BB.DISPLAY.CAPE-(BEAGLEBONE)") (pin "B9.10") (pinfunction "SYS.RESET#_B9.10") (pintype "bidirectional"))
      (node (ref "BB.DISPLAY.CAPE-(CAPE)") (pin "B9.10") (pinfunction "SYS.RESET#_B9.10") (pintype "bidirectional"))
    )
    (net (code "54") (name "/P9.11") (class "Default")
      (node (ref "BB.DISPLAY.CAPE-(BEAGLEBONE)") (pin "B9.11") (pinfunction "UART4.RXD_B9.11") (pintype "bidirectional"))
      (node (ref "BB.DISPLAY.CAPE-(CAPE)") (pin "B9.11") (pinfunction "UART4.RXD_B9.11") (pintype "bidirectional"))
    )
    (net (code "55") (name "/P9.13") (class "Default")
      (node (ref "BB.DISPLAY.CAPE-(BEAGLEBONE)") (pin "B9.13") (pinfunction "UART4.TXD_B9.13") (pintype "bidirectional"))
      (node (ref "BB.DISPLAY.CAPE-(CAPE)") (pin "B9.13") (pinfunction "UART4.TXD_B9.13") (pintype "bidirectional"))
    )
    (net (code "56") (name "/P9.14") (class "Default")
      (node (ref "BB.DISPLAY.CAPE-(BEAGLEBONE)") (pin "B9.14") (pinfunction "EHRPWM.1A_B9.14") (pintype "bidirectional"))
      (node (ref "BB.DISPLAY.CAPE-(CAPE)") (pin "B9.14") (pinfunction "EHRPWM.1A_B9.14") (pintype "bidirectional"))
    )
    (net (code "57") (name "/P9.15") (class "Default")
      (node (ref "BB.DISPLAY.CAPE-(BEAGLEBONE)") (pin "B9.15") (pinfunction "GPIO48_B9.15") (pintype "bidirectional"))
      (node (ref "BB.DISPLAY.CAPE-(CAPE)") (pin "B9.15") (pinfunction "GPIO48_B9.15") (pintype "bidirectional"))
    )
    (net (code "58") (name "/P9.16") (class "Default")
      (node (ref "BB.DISPLAY.CAPE-(BEAGLEBONE)") (pin "B9.16") (pinfunction "EHRPWM.1B_B9.16") (pintype "bidirectional"))
      (node (ref "BB.DISPLAY.CAPE-(CAPE)") (pin "B9.16") (pinfunction "EHRPWM.1B_B9.16") (pintype "bidirectional"))
    )
    (net (code "59") (name "/P9.17") (class "Default")
      (node (ref "BB.DISPLAY.CAPE-(BEAGLEBONE)") (pin "B9.17") (pinfunction "SPI0.CS0_B9.17") (pintype "bidirectional"))
      (node (ref "BB.DISPLAY.CAPE-(CAPE)") (pin "B9.17") (pinfunction "SPI0.CS0_B9.17") (pintype "bidirectional"))
    )
    (net (code "60") (name "/P9.18") (class "Default")
      (node (ref "BB.DISPLAY.CAPE-(BEAGLEBONE)") (pin "B9.18") (pinfunction "SPI0.D1_B9.18") (pintype "bidirectional"))
      (node (ref "BB.DISPLAY.CAPE-(CAPE)") (pin "B9.18") (pinfunction "SPI0.D1_B9.18") (pintype "bidirectional"))
    )
    (net (code "61") (name "/P9.21") (class "Default")
      (node (ref "BB.DISPLAY.CAPE-(BEAGLEBONE)") (pin "B9.21") (pinfunction "SPI0.D0_B9.21") (pintype "bidirectional"))
      (node (ref "BB.DISPLAY.CAPE-(CAPE)") (pin "B9.21") (pinfunction "SPI0.D0_B9.21") (pintype "bidirectional"))
    )
    (net (code "62") (name "/P9.22") (class "Default")
      (node (ref "BB.DISPLAY.CAPE-(BEAGLEBONE)") (pin "B9.22") (pinfunction "SPI0.SCK_B9.22") (pintype "bidirectional"))
      (node (ref "BB.DISPLAY.CAPE-(CAPE)") (pin "B9.22") (pinfunction "SPI0.SCK_B9.22") (pintype "bidirectional"))
    )
    (net (code "63") (name "/P9.23") (class "Default")
      (node (ref "BB.DISPLAY.CAPE-(BEAGLEBONE)") (pin "B9.23") (pinfunction "GPIO49_B9.23") (pintype "bidirectional"))
      (node (ref "BB.DISPLAY.CAPE-(CAPE)") (pin "B9.23") (pinfunction "GPIO49_B9.23") (pintype "bidirectional"))
    )
    (net (code "64") (name "/P9.24") (class "Default")
      (node (ref "BB.DISPLAY.CAPE-(BEAGLEBONE)") (pin "B9.24") (pinfunction "UART1.TXD_B9.24") (pintype "bidirectional"))
      (node (ref "BB.DISPLAY.CAPE-(CAPE)") (pin "B9.24") (pinfunction "UART1.TXD_B9.24") (pintype "bidirectional"))
    )
    (net (code "65") (name "/P9.25") (class "Default")
      (node (ref "BB.DISPLAY.CAPE-(BEAGLEBONE)") (pin "B9.25") (pinfunction "GPIO117_B9.25") (pintype "bidirectional"))
      (node (ref "BB.DISPLAY.CAPE-(CAPE)") (pin "B9.25") (pinfunction "GPIO117_B9.25") (pintype "bidirectional"))
    )
    (net (code "66") (name "/P9.26") (class "Default")
      (node (ref "BB.DISPLAY.CAPE-(BEAGLEBONE)") (pin "B9.26") (pinfunction "UART1.RXD_B9.26") (pintype "bidirectional"))
      (node (ref "BB.DISPLAY.CAPE-(CAPE)") (pin "B9.26") (pinfunction "UART1.RXD_B9.26") (pintype "bidirectional"))
    )
    (net (code "67") (name "/P9.27") (class "Default")
      (node (ref "BB.DISPLAY.CAPE-(BEAGLEBONE)") (pin "B9.27") (pinfunction "GPIO115_B9.27") (pintype "bidirectional"))
      (node (ref "BB.DISPLAY.CAPE-(CAPE)") (pin "B9.27") (pinfunction "GPIO115_B9.27") (pintype "bidirectional"))
    )
    (net (code "68") (name "/P9.28") (class "Default")
      (node (ref "BB.DISPLAY.CAPE-(BEAGLEBONE)") (pin "B9.28") (pinfunction "SPI1.CS0_B9.28") (pintype "bidirectional"))
      (node (ref "BB.DISPLAY.CAPE-(CAPE)") (pin "B9.28") (pinfunction "SPI1.CS0_B9.28") (pintype "bidirectional"))
    )
    (net (code "69") (name "/P9.29") (class "Default")
      (node (ref "BB.DISPLAY.CAPE-(BEAGLEBONE)") (pin "B9.29") (pinfunction "SPI1.D0_B9.29") (pintype "bidirectional"))
      (node (ref "BB.DISPLAY.CAPE-(CAPE)") (pin "B9.29") (pinfunction "SPI1.D0_B9.29") (pintype "bidirectional"))
    )
    (net (code "70") (name "/P9.30") (class "Default")
      (node (ref "BB.DISPLAY.CAPE-(BEAGLEBONE)") (pin "B9.30") (pinfunction "GPIO112_B9.30") (pintype "bidirectional"))
      (node (ref "BB.DISPLAY.CAPE-(CAPE)") (pin "B9.30") (pinfunction "GPIO112_B9.30") (pintype "bidirectional"))
    )
    (net (code "71") (name "/P9.31") (class "Default")
      (node (ref "BB.DISPLAY.CAPE-(BEAGLEBONE)") (pin "B9.31") (pinfunction "SPI1.SCK_B9.31") (pintype "bidirectional"))
      (node (ref "BB.DISPLAY.CAPE-(CAPE)") (pin "B9.31") (pinfunction "SPI1.SCK_B9.31") (pintype "bidirectional"))
    )
    (net (code "72") (name "/P9.32") (class "Default")
      (node (ref "BB.DISPLAY.CAPE-(BEAGLEBONE)") (pin "B9.32") (pinfunction "AVDD.ADC_B9.32") (pintype "bidirectional"))
      (node (ref "BB.DISPLAY.CAPE-(CAPE)") (pin "B9.32") (pinfunction "AVDD.ADC_B9.32") (pintype "bidirectional"))
    )
    (net (code "73") (name "/P9.33") (class "Default")
      (node (ref "BB.DISPLAY.CAPE-(BEAGLEBONE)") (pin "B9.33") (pinfunction "AIN4_B9.33") (pintype "bidirectional"))
      (node (ref "BB.DISPLAY.CAPE-(CAPE)") (pin "B9.33") (pinfunction "AIN4_B9.33") (pintype "bidirectional"))
    )
    (net (code "74") (name "/P9.34") (class "Default")
      (node (ref "BB.DISPLAY.CAPE-(BEAGLEBONE)") (pin "B9.34") (pinfunction "AGND.ADC_B9.34") (pintype "bidirectional"))
      (node (ref "BB.DISPLAY.CAPE-(CAPE)") (pin "B9.34") (pinfunction "AGND.ADC_B9.34") (pintype "bidirectional"))
    )
    (net (code "75") (name "/P9.35") (class "Default")
      (node (ref "BB.DISPLAY.CAPE-(BEAGLEBONE)") (pin "B9.35") (pinfunction "AIN6_B9.35") (pintype "bidirectional"))
      (node (ref "BB.DISPLAY.CAPE-(CAPE)") (pin "B9.35") (pinfunction "AIN6_B9.35") (pintype "bidirectional"))
    )
    (net (code "76") (name "/P9.36") (class "Default")
      (node (ref "BB.DISPLAY.CAPE-(BEAGLEBONE)") (pin "B9.36") (pinfunction "AIN5_B9.36") (pintype "bidirectional"))
      (node (ref "BB.DISPLAY.CAPE-(CAPE)") (pin "B9.36") (pinfunction "AIN5_B9.36") (pintype "bidirectional"))
    )
    (net (code "77") (name "/P9.37") (class "Default")
      (node (ref "BB.DISPLAY.CAPE-(BEAGLEBONE)") (pin "B9.37") (pinfunction "AIN2_B9.37") (pintype "bidirectional"))
      (node (ref "BB.DISPLAY.CAPE-(CAPE)") (pin "B9.37") (pinfunction "AIN2_B9.37") (pintype "bidirectional"))
    )
    (net (code "78") (name "/P9.38") (class "Default")
      (node (ref "BB.DISPLAY.CAPE-(BEAGLEBONE)") (pin "B9.38") (pinfunction "AIN3_B9.38") (pintype "bidirectional"))
      (node (ref "BB.DISPLAY.CAPE-(CAPE)") (pin "B9.38") (pinfunction "AIN3_B9.38") (pintype "bidirectional"))
    )
    (net (code "79") (name "/P9.39") (class "Default")
      (node (ref "BB.DISPLAY.CAPE-(BEAGLEBONE)") (pin "B9.39") (pinfunction "AIN0_B9.39") (pintype "bidirectional"))
      (node (ref "BB.DISPLAY.CAPE-(CAPE)") (pin "B9.39") (pinfunction "AIN0_B9.39") (pintype "bidirectional"))
    )
    (net (code "80") (name "/P9.40") (class "Default")
      (node (ref "BB.DISPLAY.CAPE-(BEAGLEBONE)") (pin "B9.40") (pinfunction "AIN1_B9.40") (pintype "bidirectional"))
      (node (ref "BB.DISPLAY.CAPE-(CAPE)") (pin "B9.40") (pinfunction "AIN1_B9.40") (pintype "bidirectional"))
    )
    (net (code "81") (name "/P9.41") (class "Default")
      (node (ref "BB.DISPLAY.CAPE-(BEAGLEBONE)") (pin "B9.41") (pinfunction "GPIO20_B9.41") (pintype "bidirectional"))
      (node (ref "BB.DISPLAY.CAPE-(CAPE)") (pin "B9.41") (pinfunction "GPIO20_B9.41") (pintype "bidirectional"))
    )
    (net (code "82") (name "/P9.42") (class "Default")
      (node (ref "BB.DISPLAY.CAPE-(BEAGLEBONE)") (pin "B9.42") (pinfunction "ECAPPWM0_B9.42") (pintype "bidirectional"))
      (node (ref "BB.DISPLAY.CAPE-(CAPE)") (pin "B9.42") (pinfunction "ECAPPWM0_B9.42") (pintype "bidirectional"))
    )
    (net (code "83") (name "/PUMP") (class "Default")
      (node (ref "D2") (pin "A") (pinfunction "ANODE_A") (pintype "bidirectional"))
      (node (ref "IC1") (pin "5") (pinfunction "SW_5") (pintype "bidirectional"))
      (node (ref "L2") (pin "2") (pinfunction "2_2") (pintype "bidirectional"))
    )
    (net (code "84") (name "/VDD.5V") (class "Default")
      (node (ref "BB.DISPLAY.CAPE-(BEAGLEBONE)") (pin "B9.5") (pinfunction "VDD.5V(1)_B9.5") (pintype "bidirectional"))
      (node (ref "BB.DISPLAY.CAPE-(BEAGLEBONE)") (pin "B9.6") (pinfunction "VDD.5V(2)_B9.6") (pintype "bidirectional"))
      (node (ref "BB.DISPLAY.CAPE-(CAPE)") (pin "B9.5") (pinfunction "VDD.5V(1)_B9.5") (pintype "bidirectional"))
      (node (ref "BB.DISPLAY.CAPE-(CAPE)") (pin "B9.6") (pinfunction "VDD.5V(2)_B9.6") (pintype "bidirectional"))
    )
    (net (code "85") (name "/WAKE") (class "Default")
      (node (ref "4.3") (pin "4") (pinfunction "4_4") (pintype "bidirectional"))
      (node (ref "5.0") (pin "4") (pinfunction "4_4") (pintype "bidirectional"))
      (node (ref "TP1") (pin "P$1") (pinfunction "TP_P$1") (pintype "bidirectional"))
    )
    (net (code "86") (name "GND") (class "Default")
      (node (ref "4.3") (pin "6") (pinfunction "6_6") (pintype "bidirectional"))
      (node (ref "5.0") (pin "6") (pinfunction "6_6") (pintype "bidirectional"))
      (node (ref "BB.DISPLAY.CAPE-(BEAGLEBONE)") (pin "B8.1") (pinfunction "DGND1_B8.1") (pintype "bidirectional"))
      (node (ref "BB.DISPLAY.CAPE-(BEAGLEBONE)") (pin "B8.2") (pinfunction "DGND2_B8.2") (pintype "bidirectional"))
      (node (ref "BB.DISPLAY.CAPE-(BEAGLEBONE)") (pin "B9.1") (pinfunction "DGND1_B9.1") (pintype "bidirectional"))
      (node (ref "BB.DISPLAY.CAPE-(BEAGLEBONE)") (pin "B9.2") (pinfunction "DGND2_B9.2") (pintype "bidirectional"))
      (node (ref "BB.DISPLAY.CAPE-(BEAGLEBONE)") (pin "B9.43") (pinfunction "DGND3_B9.43") (pintype "bidirectional"))
      (node (ref "BB.DISPLAY.CAPE-(BEAGLEBONE)") (pin "B9.44") (pinfunction "DGND4_B9.44") (pintype "bidirectional"))
      (node (ref "BB.DISPLAY.CAPE-(BEAGLEBONE)") (pin "B9.45") (pinfunction "DGND5_B9.45") (pintype "bidirectional"))
      (node (ref "BB.DISPLAY.CAPE-(BEAGLEBONE)") (pin "B9.46") (pinfunction "DGND6_B9.46") (pintype "bidirectional"))
      (node (ref "BB.DISPLAY.CAPE-(CAPE)") (pin "B8.1") (pinfunction "DGND1_B8.1") (pintype "bidirectional"))
      (node (ref "BB.DISPLAY.CAPE-(CAPE)") (pin "B8.2") (pinfunction "DGND2_B8.2") (pintype "bidirectional"))
      (node (ref "BB.DISPLAY.CAPE-(CAPE)") (pin "B9.1") (pinfunction "DGND1_B9.1") (pintype "bidirectional"))
      (node (ref "BB.DISPLAY.CAPE-(CAPE)") (pin "B9.2") (pinfunction "DGND2_B9.2") (pintype "bidirectional"))
      (node (ref "BB.DISPLAY.CAPE-(CAPE)") (pin "B9.43") (pinfunction "DGND3_B9.43") (pintype "bidirectional"))
      (node (ref "BB.DISPLAY.CAPE-(CAPE)") (pin "B9.44") (pinfunction "DGND4_B9.44") (pintype "bidirectional"))
      (node (ref "BB.DISPLAY.CAPE-(CAPE)") (pin "B9.45") (pinfunction "DGND5_B9.45") (pintype "bidirectional"))
      (node (ref "BB.DISPLAY.CAPE-(CAPE)") (pin "B9.46") (pinfunction "DGND6_B9.46") (pintype "bidirectional"))
      (node (ref "C1") (pin "2") (pinfunction "2_2") (pintype "passive"))
      (node (ref "C2") (pin "2") (pinfunction "2_2") (pintype "passive"))
      (node (ref "C3") (pin "2") (pinfunction "2_2") (pintype "passive"))
      (node (ref "C4") (pin "2") (pinfunction "2_2") (pintype "passive"))
      (node (ref "C5") (pin "2") (pinfunction "2_2") (pintype "bidirectional"))
      (node (ref "C6") (pin "2") (pinfunction "2_2") (pintype "passive"))
      (node (ref "C7") (pin "2") (pinfunction "2_2") (pintype "bidirectional"))
      (node (ref "C8") (pin "2") (pinfunction "2_2") (pintype "bidirectional"))
      (node (ref "C9") (pin "2") (pinfunction "2_2") (pintype "bidirectional"))
      (node (ref "IC1") (pin "2") (pinfunction "GND_2") (pintype "bidirectional"))
      (node (ref "IC1") (pin "THERMAL") (pinfunction "GND_THERMAL") (pintype "bidirectional"))
      (node (ref "IC2") (pin "2") (pinfunction "GND_2") (pintype "bidirectional"))
      (node (ref "IC3") (pin "4") (pinfunction "VSS_4") (pintype "bidirectional"))
      (node (ref "JMP1") (pin "2") (pinfunction "2_2") (pintype "bidirectional"))
      (node (ref "R1") (pin "2") (pinfunction "2_2") (pintype "passive"))
      (node (ref "R2") (pin "2") (pinfunction "2_2") (pintype "passive"))
      (node (ref "SJ1") (pin "1") (pinfunction "1_1") (pintype "bidirectional"))
      (node (ref "SJ2") (pin "1") (pinfunction "1_1") (pintype "bidirectional"))
      (node (ref "X2") (pin "13") (pinfunction "GND(G0)_13") (pintype "bidirectional"))
      (node (ref "X2") (pin "14") (pinfunction "GND(G1)_14") (pintype "bidirectional"))
      (node (ref "X2") (pin "21") (pinfunction "(B0)GND_21") (pintype "bidirectional"))
      (node (ref "X2") (pin "22") (pinfunction "(B1)GND_22") (pintype "bidirectional"))
      (node (ref "X2") (pin "23") (pinfunction "(B2)GND_23") (pintype "bidirectional"))
      (node (ref "X2") (pin "29") (pinfunction "GND2_29") (pintype "bidirectional"))
      (node (ref "X2") (pin "3") (pinfunction "GND1_3") (pintype "bidirectional"))
      (node (ref "X2") (pin "36") (pinfunction "GND3_36") (pintype "bidirectional"))
      (node (ref "X2") (pin "5") (pinfunction "GND(R0)_5") (pintype "bidirectional"))
      (node (ref "X2") (pin "6") (pinfunction "GND(R1)_6") (pintype "bidirectional"))
      (node (ref "X2") (pin "7") (pinfunction "GND(R2)_7") (pintype "bidirectional"))
    )
    (net (code "87") (name "Net-(IC3-A0)") (class "Default")
      (node (ref "IC3") (pin "1") (pinfunction "A0_1") (pintype "bidirectional"))
      (node (ref "R3") (pin "2") (pinfunction "2_2") (pintype "bidirectional"))
      (node (ref "SJ1") (pin "2") (pinfunction "2_2") (pintype "bidirectional"))
    )
    (net (code "88") (name "Net-(IC3-A1)") (class "Default")
      (node (ref "IC3") (pin "2") (pinfunction "A1_2") (pintype "bidirectional"))
      (node (ref "R4") (pin "2") (pinfunction "2_2") (pintype "bidirectional"))
      (node (ref "SJ2") (pin "2") (pinfunction "2_2") (pintype "bidirectional"))
    )
    (net (code "89") (name "Net-(IC3-A2)") (class "Default")
      (node (ref "IC3") (pin "3") (pinfunction "A2_3") (pintype "bidirectional"))
      (node (ref "R5") (pin "2") (pinfunction "2_2") (pintype "bidirectional"))
    )
    (net (code "90") (name "Net-(IC3-WP)") (class "Default")
      (node (ref "IC3") (pin "7") (pinfunction "WP_7") (pintype "bidirectional"))
      (node (ref "JMP1") (pin "1") (pinfunction "1_1") (pintype "bidirectional"))
      (node (ref "R6") (pin "1") (pinfunction "1_1") (pintype "bidirectional"))
    )
    (net (code "91") (name "VCC") (class "Default")
      (node (ref "4.3") (pin "3") (pinfunction "3_3") (pintype "bidirectional"))
      (node (ref "5.0") (pin "3") (pinfunction "3_3") (pintype "bidirectional"))
      (node (ref "BB.DISPLAY.CAPE-(BEAGLEBONE)") (pin "B9.3") (pinfunction "VDD.3V3(1)_B9.3") (pintype "bidirectional"))
      (node (ref "BB.DISPLAY.CAPE-(BEAGLEBONE)") (pin "B9.4") (pinfunction "VDD.3V3(2)_B9.4") (pintype "bidirectional"))
      (node (ref "BB.DISPLAY.CAPE-(CAPE)") (pin "B9.3") (pinfunction "VDD.3V3(1)_B9.3") (pintype "bidirectional"))
      (node (ref "BB.DISPLAY.CAPE-(CAPE)") (pin "B9.4") (pinfunction "VDD.3V3(2)_B9.4") (pintype "bidirectional"))
      (node (ref "C3") (pin "1") (pinfunction "1_1") (pintype "passive"))
      (node (ref "C4") (pin "1") (pinfunction "1_1") (pintype "passive"))
      (node (ref "C7") (pin "1") (pinfunction "1_1") (pintype "bidirectional"))
      (node (ref "C8") (pin "1") (pinfunction "1_1") (pintype "bidirectional"))
      (node (ref "C9") (pin "1") (pinfunction "1_1") (pintype "bidirectional"))
      (node (ref "IC3") (pin "8") (pinfunction "VCC_8") (pintype "bidirectional"))
      (node (ref "R3") (pin "1") (pinfunction "1_1") (pintype "bidirectional"))
      (node (ref "R4") (pin "1") (pinfunction "1_1") (pintype "bidirectional"))
      (node (ref "R5") (pin "1") (pinfunction "1_1") (pintype "bidirectional"))
      (node (ref "R6") (pin "2") (pinfunction "2_2") (pintype "bidirectional"))
      (node (ref "R7") (pin "2") (pinfunction "2_2") (pintype "bidirectional"))
      (node (ref "R8") (pin "2") (pinfunction "2_2") (pintype "bidirectional"))
      (node (ref "X2") (pin "31") (pinfunction "DISP_31") (pintype "bidirectional"))
      (node (ref "X2") (pin "4") (pinfunction "VDD1_4") (pintype "bidirectional"))
    )
    (net (code "92") (name "unconnected-(FUD1-PadP$1)") (class "Default")
      (node (ref "FUD1") (pin "P$1") (pinfunction "P$1_P$1") (pintype "no_connect"))
    )
    (net (code "93") (name "unconnected-(FUD2-PadP$1)") (class "Default")
      (node (ref "FUD2") (pin "P$1") (pinfunction "P$1_P$1") (pintype "no_connect"))
    )
    (net (code "94") (name "unconnected-(FUD3-PadP$1)") (class "Default")
      (node (ref "FUD3") (pin "P$1") (pinfunction "P$1_P$1") (pintype "no_connect"))
    )
    (net (code "95") (name "unconnected-(X2-(NC)T.XL-Pad39)") (class "Default")
      (node (ref "X2") (pin "39") (pinfunction "(NC)T.XL_39") (pintype "bidirectional"))
    )
    (net (code "96") (name "unconnected-(X2-(NC)T.XR-Pad37)") (class "Default")
      (node (ref "X2") (pin "37") (pinfunction "(NC)T.XR_37") (pintype "bidirectional"))
    )
    (net (code "97") (name "unconnected-(X2-(NC)T.YD-Pad38)") (class "Default")
      (node (ref "X2") (pin "38") (pinfunction "(NC)T.YD_38") (pintype "bidirectional"))
    )
    (net (code "98") (name "unconnected-(X2-(NC)T.YU-Pad40)") (class "Default")
      (node (ref "X2") (pin "40") (pinfunction "(NC)T.YU_40") (pintype "bidirectional"))
    )
    (net (code "99") (name "unconnected-(X2-NC1-Pad35)") (class "Default")
      (node (ref "X2") (pin "35") (pinfunction "NC1_35") (pintype "bidirectional"))
    )
  )
)
